# DMX.net
KiCad netlist of a schematic drawn in EAGLE
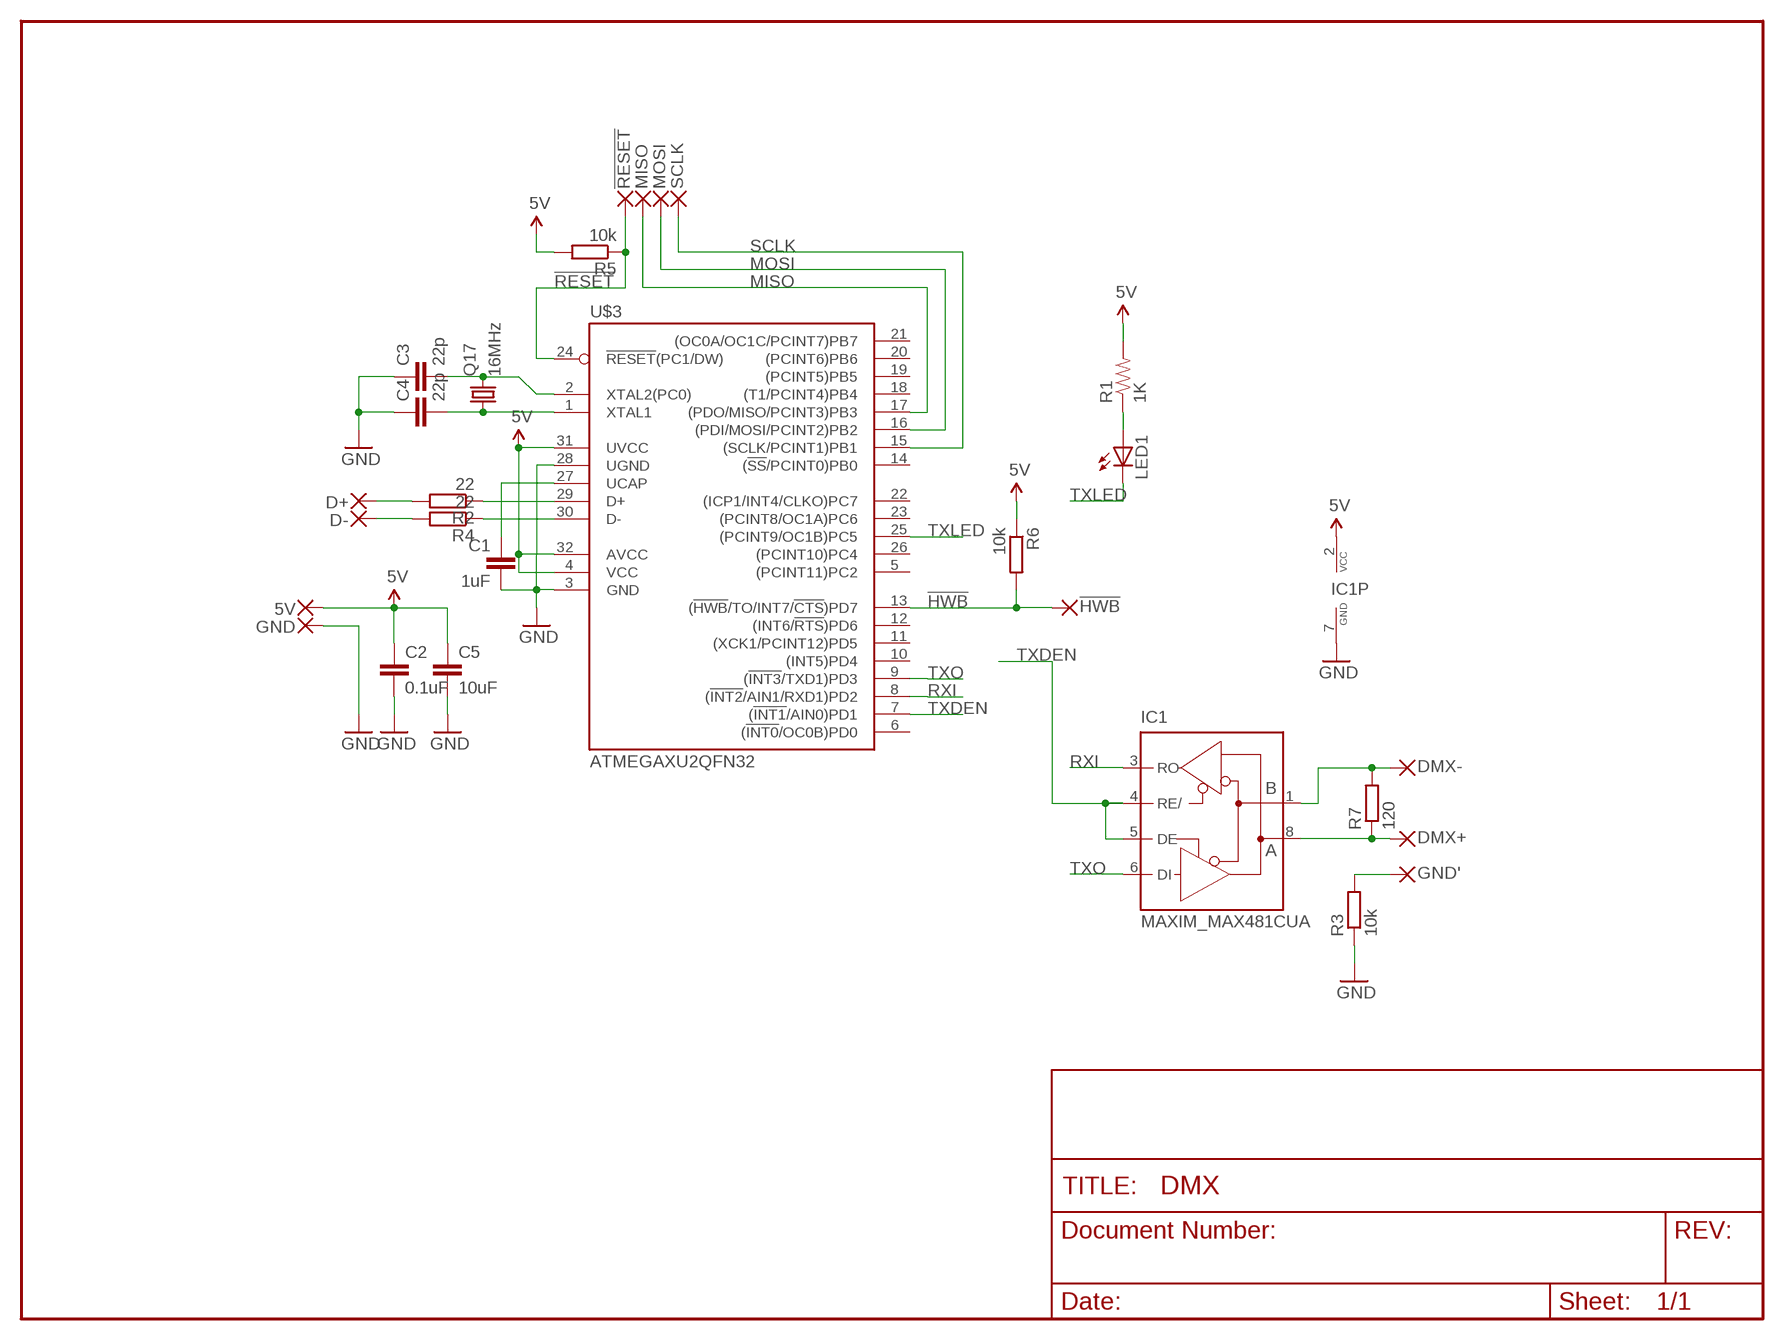
[diagram p0: schematic, sheet 1]

(export (version "E")
  (design (tool "Eeschema 10.0.6"))
  (components
    (comp (ref "!HWB")
      (value "WIREPADSMDCONTACT")
      (footprint "eagle-import:SMDCONTACT")
      (libsource (lib "eagle-import") (part "WIREPADSMDCONTACT"))
    )
    (comp (ref "!RESET")
      (value "WIREPADSMDCONTACT")
      (footprint "eagle-import:SMDCONTACT")
      (libsource (lib "eagle-import") (part "WIREPADSMDCONTACT"))
    )
    (comp (ref "5V")
      (value "WIREPAD2,15/1,0")
      (footprint "eagle-import:2,15_1,0")
      (libsource (lib "eagle-import") (part "wirepad_WIREPAD2,15/1,0"))
    )
    (comp (ref "C1")
      (value "1uF")
      (footprint "eagle-import:0603-CAP")
      (libsource (lib "eagle-import") (part "CAP0603-CAP"))
    )
    (comp (ref "C2")
      (value "0.1uF")
      (footprint "eagle-import:0603-CAP")
      (libsource (lib "eagle-import") (part "CAP0603-CAP"))
    )
    (comp (ref "C3")
      (value "22p")
      (footprint "eagle-import:C0603")
      (libsource (lib "eagle-import") (part "C-EUC0603"))
    )
    (comp (ref "C4")
      (value "22p")
      (footprint "eagle-import:C0603")
      (libsource (lib "eagle-import") (part "C-EUC0603"))
    )
    (comp (ref "C5")
      (value "10uF")
      (footprint "eagle-import:C0603K")
      (libsource (lib "eagle-import") (part "C-EUC0603K"))
    )
    (comp (ref "D+")
      (value "WIREPAD2,15/1,0")
      (footprint "eagle-import:2,15_1,0")
      (libsource (lib "eagle-import") (part "wirepad_WIREPAD2,15/1,0"))
    )
    (comp (ref "D-")
      (value "WIREPAD2,15/1,0")
      (footprint "eagle-import:2,15_1,0")
      (libsource (lib "eagle-import") (part "wirepad_WIREPAD2,15/1,0"))
    )
    (comp (ref "DMX+")
      (value "WIREPADSMD2,54-2,54")
      (footprint "eagle-import:SMD2,54-2,54")
      (libsource (lib "eagle-import") (part "WIREPADSMD2,54-2,54"))
    )
    (comp (ref "DMX-")
      (value "WIREPADSMD2,54-2,54")
      (footprint "eagle-import:SMD2,54-2,54")
      (libsource (lib "eagle-import") (part "WIREPADSMD2,54-2,54"))
    )
    (comp (ref "GND")
      (value "WIREPAD2,15/1,0")
      (footprint "eagle-import:2,15_1,0")
      (libsource (lib "eagle-import") (part "wirepad_WIREPAD2,15/1,0"))
    )
    (comp (ref "GND'")
      (value "WIREPADSMD2,54-2,54")
      (footprint "eagle-import:SMD2,54-2,54")
      (libsource (lib "eagle-import") (part "WIREPADSMD2,54-2,54"))
    )
    (comp (ref "IC1")
      (value "MAXIM_MAX481CUA")
      (footprint "eagle-import:MAXIM_UMAX8")
      (libsource (lib "eagle-import") (part "MAXIM_MAX481CUA"))
    )
    (comp (ref "LED1")
      (value "LEDSML0805")
      (footprint "eagle-import:SML0805")
      (libsource (lib "eagle-import") (part "LEDSML0805"))
    )
    (comp (ref "MISO")
      (value "WIREPADSMDCONTACT")
      (footprint "eagle-import:SMDCONTACT")
      (libsource (lib "eagle-import") (part "WIREPADSMDCONTACT"))
    )
    (comp (ref "MOSI")
      (value "WIREPADSMDCONTACT")
      (footprint "eagle-import:SMDCONTACT")
      (libsource (lib "eagle-import") (part "WIREPADSMDCONTACT"))
    )
    (comp (ref "Q17")
      (value "16MHz")
      (footprint "eagle-import:TXC-7M")
      (libsource (lib "eagle-import") (part "CRYSTAL7M"))
    )
    (comp (ref "R1")
      (value "1K")
      (footprint "eagle-import:0603-RES")
      (libsource (lib "eagle-import") (part "RESISTOR0603-RES"))
    )
    (comp (ref "R2")
      (value "22")
      (footprint "eagle-import:R0603")
      (libsource (lib "eagle-import") (part "R-EU_R0603"))
    )
    (comp (ref "R3")
      (value "10k")
      (footprint "eagle-import:R0603")
      (libsource (lib "eagle-import") (part "R-EU_R0603"))
    )
    (comp (ref "R4")
      (value "22")
      (footprint "eagle-import:R0603")
      (libsource (lib "eagle-import") (part "R-EU_R0603"))
    )
    (comp (ref "R5")
      (value "10k")
      (footprint "eagle-import:R0603")
      (libsource (lib "eagle-import") (part "R-EU_R0603"))
    )
    (comp (ref "R6")
      (value "10k")
      (footprint "eagle-import:R0603")
      (libsource (lib "eagle-import") (part "R-EU_R0603"))
    )
    (comp (ref "R7")
      (value "120")
      (footprint "eagle-import:R0603")
      (libsource (lib "eagle-import") (part "R-EU_R0603"))
    )
    (comp (ref "SCLK")
      (value "WIREPADSMDCONTACT")
      (footprint "eagle-import:SMDCONTACT")
      (libsource (lib "eagle-import") (part "WIREPADSMDCONTACT"))
    )
    (comp (ref "U$3")
      (value "ATMEGAXU2QFN32")
      (footprint "eagle-import:RHB_S-PQFP-N32")
      (libsource (lib "eagle-import") (part "ATMEGAXU2QFN32"))
    )
  )
  (nets
    (net (code "1") (name "/MISO") (class "Default")
      (node (ref "MISO") (pin "1") (pinfunction "P_1") (pintype "passive"))
      (node (ref "U$3") (pin "17") (pinfunction "(PDO/MISO/PCINT3)PB3_17") (pintype "bidirectional"))
    )
    (net (code "2") (name "/MOSI") (class "Default")
      (node (ref "MOSI") (pin "1") (pinfunction "P_1") (pintype "passive"))
      (node (ref "U$3") (pin "16") (pinfunction "(PDI/MOSI/PCINT2)PB2_16") (pintype "bidirectional"))
    )
    (net (code "3") (name "/RXI") (class "Default")
      (node (ref "IC1") (pin "3") (pinfunction "RO_3") (pintype "output"))
      (node (ref "U$3") (pin "8") (pinfunction "(~{INT2}/AIN1/RXD1)PD2_8") (pintype "bidirectional"))
    )
    (net (code "4") (name "/SCLK") (class "Default")
      (node (ref "SCLK") (pin "1") (pinfunction "P_1") (pintype "passive"))
      (node (ref "U$3") (pin "15") (pinfunction "(SCLK/PCINT1)PB1_15") (pintype "bidirectional"))
    )
    (net (code "5") (name "/TXDEN") (class "Default")
      (node (ref "IC1") (pin "4") (pinfunction "RE/_4") (pintype "input"))
      (node (ref "IC1") (pin "5") (pinfunction "DE_5") (pintype "input"))
      (node (ref "U$3") (pin "7") (pinfunction "(~{INT1}/AIN0)PD1_7") (pintype "bidirectional"))
    )
    (net (code "6") (name "/TXLED") (class "Default")
      (node (ref "LED1") (pin "C") (pinfunction "C_C") (pintype "passive"))
      (node (ref "U$3") (pin "25") (pinfunction "(PCINT9/OC1B)PC5_25") (pintype "bidirectional"))
    )
    (net (code "7") (name "/TXO") (class "Default")
      (node (ref "IC1") (pin "6") (pinfunction "DI_6") (pintype "input"))
      (node (ref "U$3") (pin "9") (pinfunction "(~{INT3}/TXD1)PD3_9") (pintype "bidirectional"))
    )
    (net (code "8") (name "/~{HWB}") (class "Default")
      (node (ref "!HWB") (pin "1") (pinfunction "P_1") (pintype "passive"))
      (node (ref "R6") (pin "2") (pinfunction "2_2") (pintype "passive"))
      (node (ref "U$3") (pin "13") (pinfunction "(~{HWB}/TO/INT7/~{CTS})PD7_13") (pintype "bidirectional"))
    )
    (net (code "9") (name "/~{RESET}") (class "Default")
      (node (ref "!RESET") (pin "1") (pinfunction "P_1") (pintype "passive"))
      (node (ref "R5") (pin "1") (pinfunction "1_1") (pintype "passive"))
      (node (ref "U$3") (pin "24") (pinfunction "~{RESET}(PC1/DW)_24") (pintype "input"))
    )
    (net (code "10") (name "5V") (class "Default")
      (node (ref "5V") (pin "1") (pinfunction "P_1") (pintype "passive"))
      (node (ref "C2") (pin "1") (pinfunction "1_1") (pintype "passive"))
      (node (ref "C5") (pin "1") (pinfunction "1_1") (pintype "passive"))
      (node (ref "IC1") (pin "2") (pinfunction "VCC_2") (pintype "power_in"))
      (node (ref "R1") (pin "2") (pinfunction "2_2") (pintype "passive"))
      (node (ref "R5") (pin "2") (pinfunction "2_2") (pintype "passive"))
      (node (ref "R6") (pin "1") (pinfunction "1_1") (pintype "passive"))
      (node (ref "U$3") (pin "31") (pinfunction "UVCC_31") (pintype "power_in"))
      (node (ref "U$3") (pin "32") (pinfunction "AVCC_32") (pintype "power_in"))
      (node (ref "U$3") (pin "4") (pinfunction "VCC_4") (pintype "power_in"))
    )
    (net (code "11") (name "GND") (class "Default")
      (node (ref "C1") (pin "2") (pinfunction "2_2") (pintype "passive"))
      (node (ref "C2") (pin "2") (pinfunction "2_2") (pintype "passive"))
      (node (ref "C3") (pin "1") (pinfunction "1_1") (pintype "passive"))
      (node (ref "C4") (pin "1") (pinfunction "1_1") (pintype "passive"))
      (node (ref "C5") (pin "2") (pinfunction "2_2") (pintype "passive"))
      (node (ref "GND") (pin "1") (pinfunction "P_1") (pintype "passive"))
      (node (ref "IC1") (pin "7") (pinfunction "GND_7") (pintype "power_in"))
      (node (ref "R3") (pin "1") (pinfunction "1_1") (pintype "passive"))
      (node (ref "U$3") (pin "28") (pinfunction "UGND_28") (pintype "power_in"))
      (node (ref "U$3") (pin "3") (pinfunction "GND_3") (pintype "power_in"))
    )
    (net (code "12") (name "Net-(D+-P)") (class "Default")
      (node (ref "D+") (pin "1") (pinfunction "P_1") (pintype "passive"))
      (node (ref "R2") (pin "2") (pinfunction "2_2") (pintype "passive"))
    )
    (net (code "13") (name "Net-(D--P)") (class "Default")
      (node (ref "D-") (pin "1") (pinfunction "P_1") (pintype "passive"))
      (node (ref "R4") (pin "2") (pinfunction "2_2") (pintype "passive"))
    )
    (net (code "14") (name "Net-(DMX+-P)") (class "Default")
      (node (ref "DMX+") (pin "1") (pinfunction "P_1") (pintype "passive"))
      (node (ref "IC1") (pin "8") (pinfunction "A_8") (pintype "passive"))
      (node (ref "R7") (pin "1") (pinfunction "1_1") (pintype "passive"))
    )
    (net (code "15") (name "Net-(DMX--P)") (class "Default")
      (node (ref "DMX-") (pin "1") (pinfunction "P_1") (pintype "passive"))
      (node (ref "IC1") (pin "1") (pinfunction "B_1") (pintype "passive"))
      (node (ref "R7") (pin "2") (pinfunction "2_2") (pintype "passive"))
    )
    (net (code "16") (name "Net-(GND'-P)") (class "Default")
      (node (ref "GND'") (pin "1") (pinfunction "P_1") (pintype "passive"))
      (node (ref "R3") (pin "2") (pinfunction "2_2") (pintype "passive"))
    )
    (net (code "17") (name "Net-(LED1-PadA)") (class "Default")
      (node (ref "LED1") (pin "A") (pinfunction "A_A") (pintype "passive"))
      (node (ref "R1") (pin "1") (pinfunction "1_1") (pintype "passive"))
    )
    (net (code "18") (name "Net-(Q17-1)") (class "Default")
      (node (ref "C4") (pin "2") (pinfunction "2_2") (pintype "passive"))
      (node (ref "Q17") (pin "A") (pinfunction "1_A") (pintype "passive"))
      (node (ref "U$3") (pin "1") (pinfunction "XTAL1_1") (pintype "bidirectional"))
    )
    (net (code "19") (name "Net-(Q17-2)") (class "Default")
      (node (ref "C3") (pin "2") (pinfunction "2_2") (pintype "passive"))
      (node (ref "Q17") (pin "B") (pinfunction "2_B") (pintype "passive"))
      (node (ref "U$3") (pin "2") (pinfunction "XTAL2(PC0)_2") (pintype "bidirectional"))
    )
    (net (code "20") (name "Net-(U$3-D+)") (class "Default")
      (node (ref "R2") (pin "1") (pinfunction "1_1") (pintype "passive"))
      (node (ref "U$3") (pin "29") (pinfunction "D+_29") (pintype "bidirectional"))
    )
    (net (code "21") (name "Net-(U$3-D-)") (class "Default")
      (node (ref "R4") (pin "1") (pinfunction "1_1") (pintype "passive"))
      (node (ref "U$3") (pin "30") (pinfunction "D-_30") (pintype "bidirectional"))
    )
    (net (code "22") (name "Net-(U$3-UCAP)") (class "Default")
      (node (ref "C1") (pin "1") (pinfunction "1_1") (pintype "passive"))
      (node (ref "U$3") (pin "27") (pinfunction "UCAP_27") (pintype "power_in"))
    )
    (net (code "23") (name "unconnected-(U$3-(ICP1{slash}INT4{slash}CLKO)PC7-Pad22)") (class "Default")
      (node (ref "U$3") (pin "22") (pinfunction "(ICP1/INT4/CLKO)PC7_22") (pintype "bidirectional"))
    )
    (net (code "24") (name "unconnected-(U$3-(INT5)PD4-Pad10)") (class "Default")
      (node (ref "U$3") (pin "10") (pinfunction "(INT5)PD4_10") (pintype "bidirectional"))
    )
    (net (code "25") (name "unconnected-(U$3-(INT6{slash}~{RTS})PD6-Pad12)") (class "Default")
      (node (ref "U$3") (pin "12") (pinfunction "(INT6/~{RTS})PD6_12") (pintype "bidirectional"))
    )
    (net (code "26") (name "unconnected-(U$3-(OC0A{slash}OC1C{slash}PCINT7)PB7-Pad21)") (class "Default")
      (node (ref "U$3") (pin "21") (pinfunction "(OC0A/OC1C/PCINT7)PB7_21") (pintype "bidirectional"))
    )
    (net (code "27") (name "unconnected-(U$3-(PCINT5)PB5-Pad19)") (class "Default")
      (node (ref "U$3") (pin "19") (pinfunction "(PCINT5)PB5_19") (pintype "bidirectional"))
    )
    (net (code "28") (name "unconnected-(U$3-(PCINT6)PB6-Pad20)") (class "Default")
      (node (ref "U$3") (pin "20") (pinfunction "(PCINT6)PB6_20") (pintype "bidirectional"))
    )
    (net (code "29") (name "unconnected-(U$3-(PCINT8{slash}OC1A)PC6-Pad23)") (class "Default")
      (node (ref "U$3") (pin "23") (pinfunction "(PCINT8/OC1A)PC6_23") (pintype "bidirectional"))
    )
    (net (code "30") (name "unconnected-(U$3-(PCINT10)PC4-Pad26)") (class "Default")
      (node (ref "U$3") (pin "26") (pinfunction "(PCINT10)PC4_26") (pintype "bidirectional"))
    )
    (net (code "31") (name "unconnected-(U$3-(PCINT11)PC2-Pad5)") (class "Default")
      (node (ref "U$3") (pin "5") (pinfunction "(PCINT11)PC2_5") (pintype "bidirectional"))
    )
    (net (code "32") (name "unconnected-(U$3-(T1{slash}PCINT4)PB4-Pad18)") (class "Default")
      (node (ref "U$3") (pin "18") (pinfunction "(T1/PCINT4)PB4_18") (pintype "bidirectional"))
    )
    (net (code "33") (name "unconnected-(U$3-(XCK1{slash}PCINT12)PD5-Pad11)") (class "Default")
      (node (ref "U$3") (pin "11") (pinfunction "(XCK1/PCINT12)PD5_11") (pintype "bidirectional"))
    )
    (net (code "34") (name "unconnected-(U$3-(~{INT0}{slash}OC0B)PD0-Pad6)") (class "Default")
      (node (ref "U$3") (pin "6") (pinfunction "(~{INT0}/OC0B)PD0_6") (pintype "bidirectional"))
    )
    (net (code "35") (name "unconnected-(U$3-(~{SS}{slash}PCINT0)PB0-Pad14)") (class "Default")
      (node (ref "U$3") (pin "14") (pinfunction "(~{SS}/PCINT0)PB0_14") (pintype "bidirectional"))
    )
  )
)
